# QCopterMV_FMC_Sch.net
KiCad netlist of a schematic drawn in Altium Designer
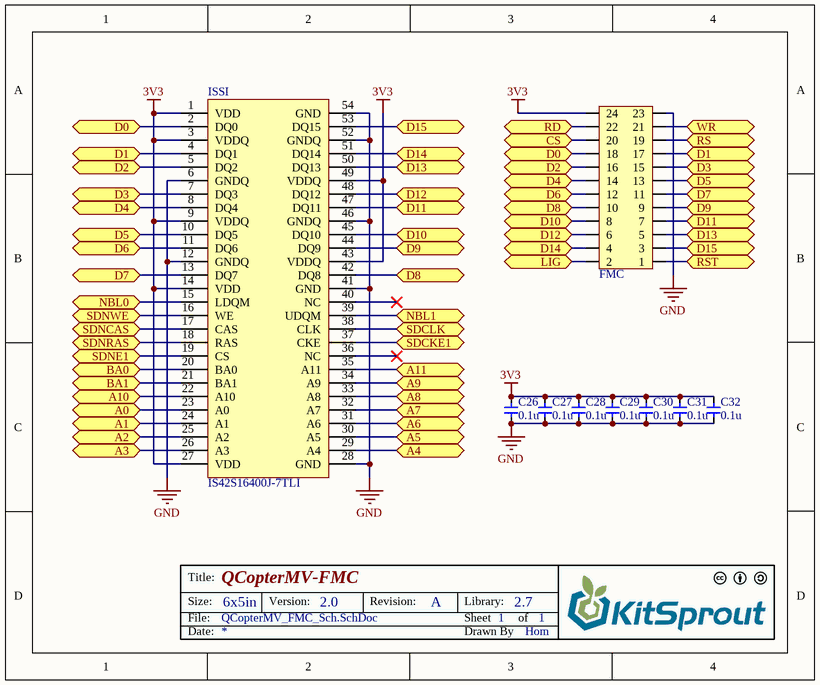
[diagram p0: QCopterMV_FMC_Sch.SchDoc]

(export (version "E")
  (design (tool "Eeschema 10.0.6"))
  (components
    (comp (ref "C26")
      (value "0.1u")
      (footprint "PCB_PassiveCap:CAP_0402")
      (description "Capacitor")
      (fields (field (name "Comment") "Cap_0402"))
      (libsource (lib "SCH_Passive") (part "Cap_0402"))
    )
    (comp (ref "C27")
      (value "0.1u")
      (footprint "PCB_PassiveCap:CAP_0402")
      (description "Capacitor")
      (fields (field (name "Comment") "Cap_0402"))
      (libsource (lib "SCH_Passive") (part "Cap_0402"))
    )
    (comp (ref "C28")
      (value "0.1u")
      (footprint "PCB_PassiveCap:CAP_0402")
      (description "Capacitor")
      (fields (field (name "Comment") "Cap_0402"))
      (libsource (lib "SCH_Passive") (part "Cap_0402"))
    )
    (comp (ref "C29")
      (value "0.1u")
      (footprint "PCB_PassiveCap:CAP_0402")
      (description "Capacitor")
      (fields (field (name "Comment") "Cap_0402"))
      (libsource (lib "SCH_Passive") (part "Cap_0402"))
    )
    (comp (ref "C30")
      (value "0.1u")
      (footprint "PCB_PassiveCap:CAP_0402")
      (description "Capacitor")
      (fields (field (name "Comment") "Cap_0402"))
      (libsource (lib "SCH_Passive") (part "Cap_0402"))
    )
    (comp (ref "C31")
      (value "0.1u")
      (footprint "PCB_PassiveCap:CAP_0402")
      (description "Capacitor")
      (fields (field (name "Comment") "Cap_0402"))
      (libsource (lib "SCH_Passive") (part "Cap_0402"))
    )
    (comp (ref "C32")
      (value "0.1u")
      (footprint "PCB_PassiveCap:CAP_0402")
      (description "Capacitor")
      (fields (field (name "Comment") "Cap_0402"))
      (libsource (lib "SCH_Passive") (part "Cap_0402"))
    )
    (comp (ref "FMC")
      (value "HDR2x12_1.27")
      (footprint "PCB_ConnectorHDR:HDR2X12_1.27_180HF")
      (description "Header")
      (libsource (lib "SCH_ConnectorHDR") (part "HDR2x12_1.27"))
    )
    (comp (ref "ISSI")
      (value "IS42S16400J-7TLI")
      (footprint "PCB_IntegratedCircuit:TSOP_E400_P0.8_54")
      (description "SDRAM")
      (libsource (lib "SCH_IntegratedCircuit") (part "IS42S16400"))
    )
  )
  (nets
    (net (code "1") (name "/A0") (class "Default")
      (node (ref "ISSI") (pin "23") (pinfunction "A0_23") (pintype "passive"))
    )
    (net (code "2") (name "/A1") (class "Default")
      (node (ref "ISSI") (pin "24") (pinfunction "A1_24") (pintype "passive"))
    )
    (net (code "3") (name "/A2") (class "Default")
      (node (ref "ISSI") (pin "25") (pinfunction "A2_25") (pintype "passive"))
    )
    (net (code "4") (name "/A3") (class "Default")
      (node (ref "ISSI") (pin "26") (pinfunction "A3_26") (pintype "passive"))
    )
    (net (code "5") (name "/A4") (class "Default")
      (node (ref "ISSI") (pin "29") (pinfunction "A4_29") (pintype "passive"))
    )
    (net (code "6") (name "/A5") (class "Default")
      (node (ref "ISSI") (pin "30") (pinfunction "A5_30") (pintype "passive"))
    )
    (net (code "7") (name "/A6") (class "Default")
      (node (ref "ISSI") (pin "31") (pinfunction "A6_31") (pintype "passive"))
    )
    (net (code "8") (name "/A7") (class "Default")
      (node (ref "ISSI") (pin "32") (pinfunction "A7_32") (pintype "passive"))
    )
    (net (code "9") (name "/A8") (class "Default")
      (node (ref "ISSI") (pin "33") (pinfunction "A8_33") (pintype "passive"))
    )
    (net (code "10") (name "/A9") (class "Default")
      (node (ref "ISSI") (pin "34") (pinfunction "A9_34") (pintype "passive"))
    )
    (net (code "11") (name "/A10") (class "Default")
      (node (ref "ISSI") (pin "22") (pinfunction "A10_22") (pintype "passive"))
    )
    (net (code "12") (name "/A11") (class "Default")
      (node (ref "ISSI") (pin "35") (pinfunction "A11_35") (pintype "passive"))
    )
    (net (code "13") (name "/BA0") (class "Default")
      (node (ref "ISSI") (pin "20") (pinfunction "BA0_20") (pintype "passive"))
    )
    (net (code "14") (name "/BA1") (class "Default")
      (node (ref "ISSI") (pin "21") (pinfunction "BA1_21") (pintype "passive"))
    )
    (net (code "15") (name "/CS") (class "Default")
      (node (ref "FMC") (pin "20") (pinfunction "20_20") (pintype "passive"))
    )
    (net (code "16") (name "/D0") (class "Default")
      (node (ref "FMC") (pin "18") (pinfunction "18_18") (pintype "passive"))
      (node (ref "ISSI") (pin "2") (pinfunction "DQ0_2") (pintype "passive"))
    )
    (net (code "17") (name "/D1") (class "Default")
      (node (ref "FMC") (pin "17") (pinfunction "17_17") (pintype "passive"))
      (node (ref "ISSI") (pin "4") (pinfunction "DQ1_4") (pintype "passive"))
    )
    (net (code "18") (name "/D2") (class "Default")
      (node (ref "FMC") (pin "16") (pinfunction "16_16") (pintype "passive"))
      (node (ref "ISSI") (pin "5") (pinfunction "DQ2_5") (pintype "passive"))
    )
    (net (code "19") (name "/D3") (class "Default")
      (node (ref "FMC") (pin "15") (pinfunction "15_15") (pintype "passive"))
      (node (ref "ISSI") (pin "7") (pinfunction "DQ3_7") (pintype "passive"))
    )
    (net (code "20") (name "/D4") (class "Default")
      (node (ref "FMC") (pin "14") (pinfunction "14_14") (pintype "passive"))
      (node (ref "ISSI") (pin "8") (pinfunction "DQ4_8") (pintype "passive"))
    )
    (net (code "21") (name "/D5") (class "Default")
      (node (ref "FMC") (pin "13") (pinfunction "13_13") (pintype "passive"))
      (node (ref "ISSI") (pin "10") (pinfunction "DQ5_10") (pintype "passive"))
    )
    (net (code "22") (name "/D6") (class "Default")
      (node (ref "FMC") (pin "12") (pinfunction "12_12") (pintype "passive"))
      (node (ref "ISSI") (pin "11") (pinfunction "DQ6_11") (pintype "passive"))
    )
    (net (code "23") (name "/D7") (class "Default")
      (node (ref "FMC") (pin "11") (pinfunction "11_11") (pintype "passive"))
      (node (ref "ISSI") (pin "13") (pinfunction "DQ7_13") (pintype "passive"))
    )
    (net (code "24") (name "/D8") (class "Default")
      (node (ref "FMC") (pin "10") (pinfunction "10_10") (pintype "passive"))
      (node (ref "ISSI") (pin "42") (pinfunction "DQ8_42") (pintype "passive"))
    )
    (net (code "25") (name "/D9") (class "Default")
      (node (ref "FMC") (pin "9") (pinfunction "9_9") (pintype "passive"))
      (node (ref "ISSI") (pin "44") (pinfunction "DQ9_44") (pintype "passive"))
    )
    (net (code "26") (name "/D10") (class "Default")
      (node (ref "FMC") (pin "8") (pinfunction "8_8") (pintype "passive"))
      (node (ref "ISSI") (pin "45") (pinfunction "DQ10_45") (pintype "passive"))
    )
    (net (code "27") (name "/D11") (class "Default")
      (node (ref "FMC") (pin "7") (pinfunction "7_7") (pintype "passive"))
      (node (ref "ISSI") (pin "47") (pinfunction "DQ11_47") (pintype "passive"))
    )
    (net (code "28") (name "/D12") (class "Default")
      (node (ref "FMC") (pin "6") (pinfunction "6_6") (pintype "passive"))
      (node (ref "ISSI") (pin "48") (pinfunction "DQ12_48") (pintype "passive"))
    )
    (net (code "29") (name "/D13") (class "Default")
      (node (ref "FMC") (pin "5") (pinfunction "5_5") (pintype "passive"))
      (node (ref "ISSI") (pin "50") (pinfunction "DQ13_50") (pintype "passive"))
    )
    (net (code "30") (name "/D14") (class "Default")
      (node (ref "FMC") (pin "4") (pinfunction "4_4") (pintype "passive"))
      (node (ref "ISSI") (pin "51") (pinfunction "DQ14_51") (pintype "passive"))
    )
    (net (code "31") (name "/D15") (class "Default")
      (node (ref "FMC") (pin "3") (pinfunction "3_3") (pintype "passive"))
      (node (ref "ISSI") (pin "53") (pinfunction "DQ15_53") (pintype "passive"))
    )
    (net (code "32") (name "/LIG") (class "Default")
      (node (ref "FMC") (pin "2") (pinfunction "2_2") (pintype "passive"))
    )
    (net (code "33") (name "/NBL0") (class "Default")
      (node (ref "ISSI") (pin "15") (pinfunction "LDQM_15") (pintype "passive"))
    )
    (net (code "34") (name "/NBL1") (class "Default")
      (node (ref "ISSI") (pin "39") (pinfunction "UDQM_39") (pintype "passive"))
    )
    (net (code "35") (name "/RD") (class "Default")
      (node (ref "FMC") (pin "22") (pinfunction "22_22") (pintype "passive"))
    )
    (net (code "36") (name "/RS") (class "Default")
      (node (ref "FMC") (pin "19") (pinfunction "19_19") (pintype "passive"))
    )
    (net (code "37") (name "/RST") (class "Default")
      (node (ref "FMC") (pin "1") (pinfunction "1_1") (pintype "passive"))
    )
    (net (code "38") (name "/SDCKE1") (class "Default")
      (node (ref "ISSI") (pin "37") (pinfunction "CKE_37") (pintype "passive"))
    )
    (net (code "39") (name "/SDCLK") (class "Default")
      (node (ref "ISSI") (pin "38") (pinfunction "CLK_38") (pintype "passive"))
    )
    (net (code "40") (name "/SDNCAS") (class "Default")
      (node (ref "ISSI") (pin "17") (pinfunction "CAS_17") (pintype "passive"))
    )
    (net (code "41") (name "/SDNE1") (class "Default")
      (node (ref "ISSI") (pin "19") (pinfunction "CS_19") (pintype "passive"))
    )
    (net (code "42") (name "/SDNRAS") (class "Default")
      (node (ref "ISSI") (pin "18") (pinfunction "RAS_18") (pintype "passive"))
    )
    (net (code "43") (name "/SDNWE") (class "Default")
      (node (ref "ISSI") (pin "16") (pinfunction "WE_16") (pintype "passive"))
    )
    (net (code "44") (name "/WR") (class "Default")
      (node (ref "FMC") (pin "21") (pinfunction "21_21") (pintype "passive"))
    )
    (net (code "45") (name "3V3") (class "Default")
      (node (ref "C26") (pin "2") (pinfunction "2_2") (pintype "passive"))
      (node (ref "C27") (pin "2") (pinfunction "2_2") (pintype "passive"))
      (node (ref "C28") (pin "2") (pinfunction "2_2") (pintype "passive"))
      (node (ref "C29") (pin "2") (pinfunction "2_2") (pintype "passive"))
      (node (ref "C30") (pin "2") (pinfunction "2_2") (pintype "passive"))
      (node (ref "C31") (pin "2") (pinfunction "2_2") (pintype "passive"))
      (node (ref "C32") (pin "2") (pinfunction "2_2") (pintype "passive"))
      (node (ref "FMC") (pin "24") (pinfunction "24_24") (pintype "passive"))
      (node (ref "ISSI") (pin "1") (pinfunction "VDD_1") (pintype "passive"))
      (node (ref "ISSI") (pin "14") (pinfunction "VDD_14") (pintype "passive"))
      (node (ref "ISSI") (pin "27") (pinfunction "VDD_27") (pintype "passive"))
      (node (ref "ISSI") (pin "3") (pinfunction "VDDQ_3") (pintype "passive"))
      (node (ref "ISSI") (pin "43") (pinfunction "VDDQ_43") (pintype "passive"))
      (node (ref "ISSI") (pin "49") (pinfunction "VDDQ_49") (pintype "passive"))
      (node (ref "ISSI") (pin "9") (pinfunction "VDDQ_9") (pintype "passive"))
    )
    (net (code "46") (name "GND") (class "Default")
      (node (ref "C26") (pin "1") (pinfunction "1_1") (pintype "passive"))
      (node (ref "C27") (pin "1") (pinfunction "1_1") (pintype "passive"))
      (node (ref "C28") (pin "1") (pinfunction "1_1") (pintype "passive"))
      (node (ref "C29") (pin "1") (pinfunction "1_1") (pintype "passive"))
      (node (ref "C30") (pin "1") (pinfunction "1_1") (pintype "passive"))
      (node (ref "C31") (pin "1") (pinfunction "1_1") (pintype "passive"))
      (node (ref "C32") (pin "1") (pinfunction "1_1") (pintype "passive"))
      (node (ref "FMC") (pin "23") (pinfunction "23_23") (pintype "passive"))
      (node (ref "ISSI") (pin "12") (pinfunction "GNDQ_12") (pintype "passive"))
      (node (ref "ISSI") (pin "28") (pinfunction "GND_28") (pintype "passive"))
      (node (ref "ISSI") (pin "41") (pinfunction "GND_41") (pintype "passive"))
      (node (ref "ISSI") (pin "46") (pinfunction "GNDQ_46") (pintype "passive"))
      (node (ref "ISSI") (pin "52") (pinfunction "GNDQ_52") (pintype "passive"))
      (node (ref "ISSI") (pin "54") (pinfunction "GND_54") (pintype "passive"))
      (node (ref "ISSI") (pin "6") (pinfunction "GNDQ_6") (pintype "passive"))
    )
    (net (code "47") (name "unconnected-(ISSI-NC-Pad36)") (class "Default")
      (node (ref "ISSI") (pin "36") (pinfunction "NC_36") (pintype "passive+no_connect"))
    )
    (net (code "48") (name "unconnected-(ISSI-NC-Pad40)") (class "Default")
      (node (ref "ISSI") (pin "40") (pinfunction "NC_40") (pintype "passive+no_connect"))
    )
  )
)
